# nor_ppalette.net
KiCad netlist of a schematic drawn in EAGLE
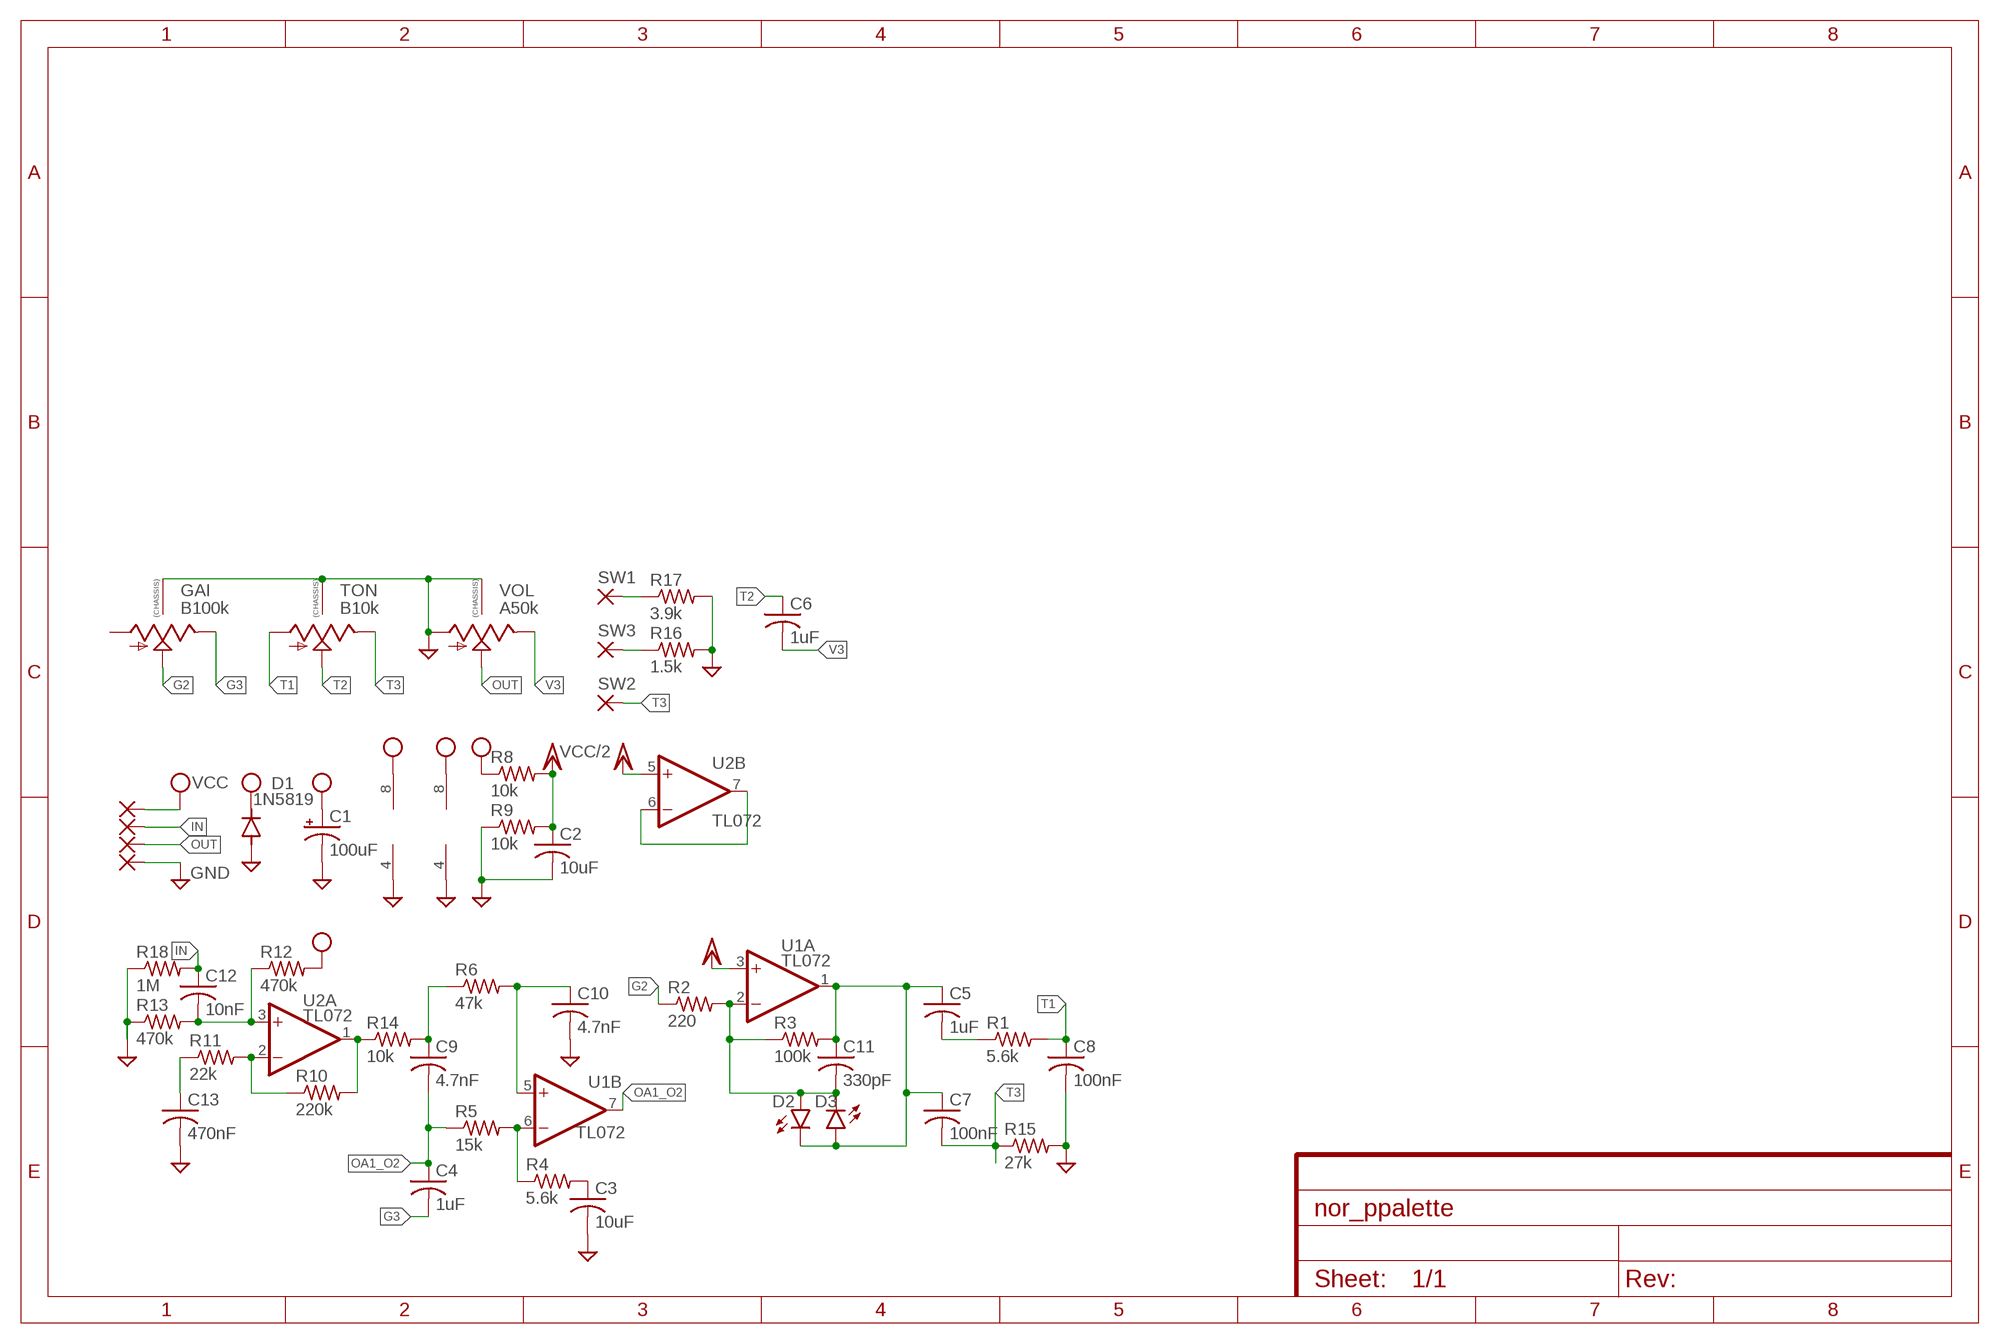
[diagram p0: schematic, sheet 1]

(export (version "E")
  (design (tool "Eeschema 10.0.6"))
  (components
    (comp (ref "C1")
      (value "100uF")
      (footprint "eagle-import:CPOL-RADIAL-2.5MM-6.5MM")
      (libsource (lib "eagle-import") (part "100UF-POLAR-RADIAL-2.5MM-25V-20%"))
    )
    (comp (ref "C2")
      (value "10uF")
      (footprint "eagle-import:C1206")
      (libsource (lib "eagle-import") (part "C-USC1206"))
    )
    (comp (ref "C3")
      (value "10uF")
      (footprint "eagle-import:C1206")
      (libsource (lib "eagle-import") (part "C-USC1206"))
    )
    (comp (ref "C4")
      (value "1uF")
      (footprint "eagle-import:C0805")
      (libsource (lib "eagle-import") (part "adafruit_420_C-USC0805"))
    )
    (comp (ref "C5")
      (value "1uF")
      (footprint "eagle-import:C0805")
      (libsource (lib "eagle-import") (part "adafruit_420_C-USC0805"))
    )
    (comp (ref "C6")
      (value "1uF")
      (footprint "eagle-import:C0805")
      (libsource (lib "eagle-import") (part "adafruit_420_C-USC0805"))
    )
    (comp (ref "C7")
      (value "100nF")
      (footprint "eagle-import:C0603")
      (libsource (lib "eagle-import") (part "adafruit_420_C-USC0603"))
    )
    (comp (ref "C8")
      (value "100nF")
      (footprint "eagle-import:C0603")
      (libsource (lib "eagle-import") (part "adafruit_420_C-USC0603"))
    )
    (comp (ref "C9")
      (value "4.7nF")
      (footprint "eagle-import:C0603")
      (libsource (lib "eagle-import") (part "adafruit_420_C-USC0603"))
    )
    (comp (ref "C10")
      (value "4.7nF")
      (footprint "eagle-import:C0603")
      (libsource (lib "eagle-import") (part "adafruit_420_C-USC0603"))
    )
    (comp (ref "C11")
      (value "330pF")
      (footprint "eagle-import:C0603")
      (libsource (lib "eagle-import") (part "adafruit_420_C-USC0603"))
    )
    (comp (ref "C12")
      (value "10nF")
      (footprint "eagle-import:C0603")
      (libsource (lib "eagle-import") (part "adafruit_420_C-USC0603"))
    )
    (comp (ref "C13")
      (value "470nF")
      (footprint "eagle-import:C0603")
      (libsource (lib "eagle-import") (part "adafruit_420_C-USC0603"))
    )
    (comp (ref "D1")
      (value "1N5819")
      (footprint "eagle-import:SOD123")
      (libsource (lib "eagle-import") (part "DIODE-SOD123"))
    )
    (comp (ref "D2")
      (value "LED0603")
      (footprint "eagle-import:LED-0603")
      (libsource (lib "eagle-import") (part "LED0603"))
    )
    (comp (ref "D3")
      (value "LED0603")
      (footprint "eagle-import:LED-0603")
      (libsource (lib "eagle-import") (part "LED0603"))
    )
    (comp (ref "GAI")
      (value "B100k")
      (footprint "eagle-import:9MM_SNAP-IN_POT")
      (libsource (lib "eagle-import") (part "9MM_SNAP-IN_POT_CHASSIS"))
    )
    (comp (ref "PAD1")
      (value "1,6/0,8")
      (footprint "eagle-import:1,6_0,8")
      (libsource (lib "eagle-import") (part "1,6/0,8"))
    )
    (comp (ref "PAD2")
      (value "1,6/0,8")
      (footprint "eagle-import:1,6_0,8")
      (libsource (lib "eagle-import") (part "1,6/0,8"))
    )
    (comp (ref "PAD3")
      (value "1,6/0,8")
      (footprint "eagle-import:1,6_0,8")
      (libsource (lib "eagle-import") (part "1,6/0,8"))
    )
    (comp (ref "PAD4")
      (value "1,6/0,8")
      (footprint "eagle-import:1,6_0,8")
      (libsource (lib "eagle-import") (part "1,6/0,8"))
    )
    (comp (ref "R1")
      (value "5.6k")
      (footprint "eagle-import:R0603")
      (libsource (lib "eagle-import") (part "R-US_R0603"))
    )
    (comp (ref "R2")
      (value "220")
      (footprint "eagle-import:R0603")
      (libsource (lib "eagle-import") (part "R-US_R0603"))
    )
    (comp (ref "R3")
      (value "100k")
      (footprint "eagle-import:R0603")
      (libsource (lib "eagle-import") (part "R-US_R0603"))
    )
    (comp (ref "R4")
      (value "5.6k")
      (footprint "eagle-import:R0603")
      (libsource (lib "eagle-import") (part "R-US_R0603"))
    )
    (comp (ref "R5")
      (value "15k")
      (footprint "eagle-import:R0603")
      (libsource (lib "eagle-import") (part "R-US_R0603"))
    )
    (comp (ref "R6")
      (value "47k")
      (footprint "eagle-import:R0603")
      (libsource (lib "eagle-import") (part "R-US_R0603"))
    )
    (comp (ref "R8")
      (value "10k")
      (footprint "eagle-import:R0603")
      (libsource (lib "eagle-import") (part "R-US_R0603"))
    )
    (comp (ref "R9")
      (value "10k")
      (footprint "eagle-import:R0603")
      (libsource (lib "eagle-import") (part "R-US_R0603"))
    )
    (comp (ref "R10")
      (value "220k")
      (footprint "eagle-import:R0603")
      (libsource (lib "eagle-import") (part "R-US_R0603"))
    )
    (comp (ref "R11")
      (value "22k")
      (footprint "eagle-import:R0603")
      (libsource (lib "eagle-import") (part "R-US_R0603"))
    )
    (comp (ref "R12")
      (value "470k")
      (footprint "eagle-import:R0603")
      (libsource (lib "eagle-import") (part "R-US_R0603"))
    )
    (comp (ref "R13")
      (value "470k")
      (footprint "eagle-import:R0603")
      (libsource (lib "eagle-import") (part "R-US_R0603"))
    )
    (comp (ref "R14")
      (value "10k")
      (footprint "eagle-import:R0603")
      (libsource (lib "eagle-import") (part "R-US_R0603"))
    )
    (comp (ref "R15")
      (value "27k")
      (footprint "eagle-import:R0603")
      (libsource (lib "eagle-import") (part "R-US_R0603"))
    )
    (comp (ref "R16")
      (value "1.5k")
      (footprint "eagle-import:R0603")
      (libsource (lib "eagle-import") (part "R-US_R0603"))
    )
    (comp (ref "R17")
      (value "3.9k")
      (footprint "eagle-import:R0603")
      (libsource (lib "eagle-import") (part "R-US_R0603"))
    )
    (comp (ref "R18")
      (value "1M")
      (footprint "eagle-import:R0603")
      (libsource (lib "eagle-import") (part "R-US_R0603"))
    )
    (comp (ref "SW1")
      (value "1,6/0,8")
      (footprint "eagle-import:1,6_0,8")
      (libsource (lib "eagle-import") (part "1,6/0,8"))
    )
    (comp (ref "SW2")
      (value "1,6/0,8")
      (footprint "eagle-import:1,6_0,8")
      (libsource (lib "eagle-import") (part "1,6/0,8"))
    )
    (comp (ref "SW3")
      (value "1,6/0,8")
      (footprint "eagle-import:1,6_0,8")
      (libsource (lib "eagle-import") (part "1,6/0,8"))
    )
    (comp (ref "TON")
      (value "B10k")
      (footprint "eagle-import:9MM_SNAP-IN_POT")
      (libsource (lib "eagle-import") (part "9MM_SNAP-IN_POT_CHASSIS"))
    )
    (comp (ref "U1")
      (value "TL072")
      (footprint "eagle-import:TSSOP-8")
      (libsource (lib "eagle-import") (part "TL072TSSOP"))
    )
    (comp (ref "U2")
      (value "TL072")
      (footprint "eagle-import:TSSOP-8")
      (libsource (lib "eagle-import") (part "TL072TSSOP"))
    )
    (comp (ref "VOL")
      (value "A50k")
      (footprint "eagle-import:9MM_SNAP-IN_POT")
      (libsource (lib "eagle-import") (part "9MM_SNAP-IN_POT_CHASSIS"))
    )
  )
  (nets
    (net (code "1") (name "G2") (class "Default")
      (node (ref "GAI") (pin "2") (pinfunction "S_2") (pintype "passive"))
      (node (ref "R2") (pin "1") (pinfunction "1_1") (pintype "passive"))
    )
    (net (code "2") (name "G3") (class "Default")
      (node (ref "C4") (pin "2") (pinfunction "2_2") (pintype "passive"))
      (node (ref "GAI") (pin "3") (pinfunction "E_3") (pintype "passive"))
    )
    (net (code "3") (name "GND") (class "Default")
      (node (ref "C1") (pin "2") (pinfunction "-_2") (pintype "passive"))
      (node (ref "C10") (pin "2") (pinfunction "2_2") (pintype "passive"))
      (node (ref "C13") (pin "2") (pinfunction "2_2") (pintype "passive"))
      (node (ref "C2") (pin "2") (pinfunction "2_2") (pintype "passive"))
      (node (ref "C3") (pin "2") (pinfunction "2_2") (pintype "passive"))
      (node (ref "C8") (pin "2") (pinfunction "2_2") (pintype "passive"))
      (node (ref "D1") (pin "A") (pinfunction "A_A") (pintype "passive"))
      (node (ref "GAI") (pin "CHASSIS1") (pinfunction "P$1_CHASSIS1") (pintype "passive"))
      (node (ref "GAI") (pin "CHASSIS2") (pinfunction "P$1_CHASSIS2") (pintype "passive"))
      (node (ref "PAD4") (pin "1") (pinfunction "P_1") (pintype "passive"))
      (node (ref "R13") (pin "1") (pinfunction "1_1") (pintype "passive"))
      (node (ref "R15") (pin "2") (pinfunction "2_2") (pintype "passive"))
      (node (ref "R16") (pin "2") (pinfunction "2_2") (pintype "passive"))
      (node (ref "R17") (pin "2") (pinfunction "2_2") (pintype "passive"))
      (node (ref "R18") (pin "1") (pinfunction "1_1") (pintype "passive"))
      (node (ref "R9") (pin "1") (pinfunction "1_1") (pintype "passive"))
      (node (ref "TON") (pin "CHASSIS1") (pinfunction "P$1_CHASSIS1") (pintype "passive"))
      (node (ref "TON") (pin "CHASSIS2") (pinfunction "P$1_CHASSIS2") (pintype "passive"))
      (node (ref "U1") (pin "4") (pinfunction "V-_4") (pintype "power_in"))
      (node (ref "U2") (pin "4") (pinfunction "V-_4") (pintype "power_in"))
      (node (ref "VOL") (pin "1") (pinfunction "A_1") (pintype "passive"))
      (node (ref "VOL") (pin "CHASSIS1") (pinfunction "P$1_CHASSIS1") (pintype "passive"))
      (node (ref "VOL") (pin "CHASSIS2") (pinfunction "P$1_CHASSIS2") (pintype "passive"))
    )
    (net (code "4") (name "IN") (class "Default")
      (node (ref "C12") (pin "1") (pinfunction "1_1") (pintype "passive"))
      (node (ref "PAD2") (pin "1") (pinfunction "P_1") (pintype "passive"))
      (node (ref "R18") (pin "2") (pinfunction "2_2") (pintype "passive"))
    )
    (net (code "5") (name "Net-(C3-Pad1)") (class "Default")
      (node (ref "C3") (pin "1") (pinfunction "1_1") (pintype "passive"))
      (node (ref "R4") (pin "2") (pinfunction "2_2") (pintype "passive"))
    )
    (net (code "6") (name "Net-(C5-Pad2)") (class "Default")
      (node (ref "C5") (pin "2") (pinfunction "2_2") (pintype "passive"))
      (node (ref "R1") (pin "1") (pinfunction "1_1") (pintype "passive"))
    )
    (net (code "7") (name "Net-(C9-Pad1)") (class "Default")
      (node (ref "C9") (pin "1") (pinfunction "1_1") (pintype "passive"))
      (node (ref "R14") (pin "2") (pinfunction "2_2") (pintype "passive"))
      (node (ref "R6") (pin "1") (pinfunction "1_1") (pintype "passive"))
    )
    (net (code "8") (name "Net-(C13-Pad1)") (class "Default")
      (node (ref "C13") (pin "1") (pinfunction "1_1") (pintype "passive"))
      (node (ref "R11") (pin "1") (pinfunction "1_1") (pintype "passive"))
    )
    (net (code "9") (name "Net-(SW1-P)") (class "Default")
      (node (ref "R17") (pin "1") (pinfunction "1_1") (pintype "passive"))
      (node (ref "SW1") (pin "1") (pinfunction "P_1") (pintype "passive"))
    )
    (net (code "10") (name "Net-(SW3-P)") (class "Default")
      (node (ref "R16") (pin "1") (pinfunction "1_1") (pintype "passive"))
      (node (ref "SW3") (pin "1") (pinfunction "P_1") (pintype "passive"))
    )
    (net (code "11") (name "Net-(U1A--IN)") (class "Default")
      (node (ref "C11") (pin "2") (pinfunction "2_2") (pintype "passive"))
      (node (ref "D2") (pin "A") (pinfunction "A_A") (pintype "passive"))
      (node (ref "D3") (pin "C") (pinfunction "C_C") (pintype "passive"))
      (node (ref "R2") (pin "2") (pinfunction "2_2") (pintype "passive"))
      (node (ref "R3") (pin "1") (pinfunction "1_1") (pintype "passive"))
      (node (ref "U1") (pin "2") (pinfunction "-IN_2") (pintype "input"))
    )
    (net (code "12") (name "Net-(U1A-OUT)") (class "Default")
      (node (ref "C11") (pin "1") (pinfunction "1_1") (pintype "passive"))
      (node (ref "C5") (pin "1") (pinfunction "1_1") (pintype "passive"))
      (node (ref "C7") (pin "1") (pinfunction "1_1") (pintype "passive"))
      (node (ref "D2") (pin "C") (pinfunction "C_C") (pintype "passive"))
      (node (ref "D3") (pin "A") (pinfunction "A_A") (pintype "passive"))
      (node (ref "R3") (pin "2") (pinfunction "2_2") (pintype "passive"))
      (node (ref "U1") (pin "1") (pinfunction "OUT_1") (pintype "output"))
    )
    (net (code "13") (name "Net-(U1B-+IN)") (class "Default")
      (node (ref "C10") (pin "1") (pinfunction "1_1") (pintype "passive"))
      (node (ref "R6") (pin "2") (pinfunction "2_2") (pintype "passive"))
      (node (ref "U1") (pin "5") (pinfunction "+IN_5") (pintype "input"))
    )
    (net (code "14") (name "Net-(U1B--IN)") (class "Default")
      (node (ref "R4") (pin "1") (pinfunction "1_1") (pintype "passive"))
      (node (ref "R5") (pin "2") (pinfunction "2_2") (pintype "passive"))
      (node (ref "U1") (pin "6") (pinfunction "-IN_6") (pintype "input"))
    )
    (net (code "15") (name "Net-(U2A-+IN)") (class "Default")
      (node (ref "C12") (pin "2") (pinfunction "2_2") (pintype "passive"))
      (node (ref "R12") (pin "1") (pinfunction "1_1") (pintype "passive"))
      (node (ref "R13") (pin "2") (pinfunction "2_2") (pintype "passive"))
      (node (ref "U2") (pin "3") (pinfunction "+IN_3") (pintype "input"))
    )
    (net (code "16") (name "Net-(U2A--IN)") (class "Default")
      (node (ref "R10") (pin "1") (pinfunction "1_1") (pintype "passive"))
      (node (ref "R11") (pin "2") (pinfunction "2_2") (pintype "passive"))
      (node (ref "U2") (pin "2") (pinfunction "-IN_2") (pintype "input"))
    )
    (net (code "17") (name "Net-(U2A-OUT)") (class "Default")
      (node (ref "R10") (pin "2") (pinfunction "2_2") (pintype "passive"))
      (node (ref "R14") (pin "1") (pinfunction "1_1") (pintype "passive"))
      (node (ref "U2") (pin "1") (pinfunction "OUT_1") (pintype "output"))
    )
    (net (code "18") (name "Net-(U2B--IN)") (class "Default")
      (node (ref "U2") (pin "6") (pinfunction "-IN_6") (pintype "input"))
      (node (ref "U2") (pin "7") (pinfunction "OUT_7") (pintype "output"))
    )
    (net (code "19") (name "OA1_O2") (class "Default")
      (node (ref "C4") (pin "1") (pinfunction "1_1") (pintype "passive"))
      (node (ref "C9") (pin "2") (pinfunction "2_2") (pintype "passive"))
      (node (ref "R5") (pin "1") (pinfunction "1_1") (pintype "passive"))
      (node (ref "U1") (pin "7") (pinfunction "OUT_7") (pintype "output"))
    )
    (net (code "20") (name "OUT") (class "Default")
      (node (ref "PAD3") (pin "1") (pinfunction "P_1") (pintype "passive"))
      (node (ref "VOL") (pin "2") (pinfunction "S_2") (pintype "passive"))
    )
    (net (code "21") (name "T1") (class "Default")
      (node (ref "C8") (pin "1") (pinfunction "1_1") (pintype "passive"))
      (node (ref "R1") (pin "2") (pinfunction "2_2") (pintype "passive"))
      (node (ref "TON") (pin "1") (pinfunction "A_1") (pintype "passive"))
    )
    (net (code "22") (name "T2") (class "Default")
      (node (ref "C6") (pin "1") (pinfunction "1_1") (pintype "passive"))
      (node (ref "TON") (pin "2") (pinfunction "S_2") (pintype "passive"))
    )
    (net (code "23") (name "T3") (class "Default")
      (node (ref "C7") (pin "2") (pinfunction "2_2") (pintype "passive"))
      (node (ref "R15") (pin "1") (pinfunction "1_1") (pintype "passive"))
      (node (ref "SW2") (pin "1") (pinfunction "P_1") (pintype "passive"))
      (node (ref "TON") (pin "3") (pinfunction "E_3") (pintype "passive"))
    )
    (net (code "24") (name "V3") (class "Default")
      (node (ref "C6") (pin "2") (pinfunction "2_2") (pintype "passive"))
      (node (ref "VOL") (pin "3") (pinfunction "E_3") (pintype "passive"))
    )
    (net (code "25") (name "VCC") (class "Default")
      (node (ref "C1") (pin "1") (pinfunction "+_1") (pintype "passive"))
      (node (ref "D1") (pin "C") (pinfunction "C_C") (pintype "passive"))
      (node (ref "PAD1") (pin "1") (pinfunction "P_1") (pintype "passive"))
      (node (ref "R12") (pin "2") (pinfunction "2_2") (pintype "passive"))
      (node (ref "R8") (pin "1") (pinfunction "1_1") (pintype "passive"))
      (node (ref "U1") (pin "8") (pinfunction "V+_8") (pintype "power_in"))
      (node (ref "U2") (pin "8") (pinfunction "V+_8") (pintype "power_in"))
    )
    (net (code "26") (name "VCC{slash}2") (class "Default")
      (node (ref "C2") (pin "1") (pinfunction "1_1") (pintype "passive"))
      (node (ref "R8") (pin "2") (pinfunction "2_2") (pintype "passive"))
      (node (ref "R9") (pin "2") (pinfunction "2_2") (pintype "passive"))
      (node (ref "U1") (pin "3") (pinfunction "+IN_3") (pintype "input"))
      (node (ref "U2") (pin "5") (pinfunction "+IN_5") (pintype "input"))
    )
    (net (code "27") (name "unconnected-(GAI-A-Pad1)") (class "Default")
      (node (ref "GAI") (pin "1") (pinfunction "A_1") (pintype "passive"))
    )
  )
)
